# v5-Power-Section.net
KiCad netlist of a schematic drawn in EAGLE
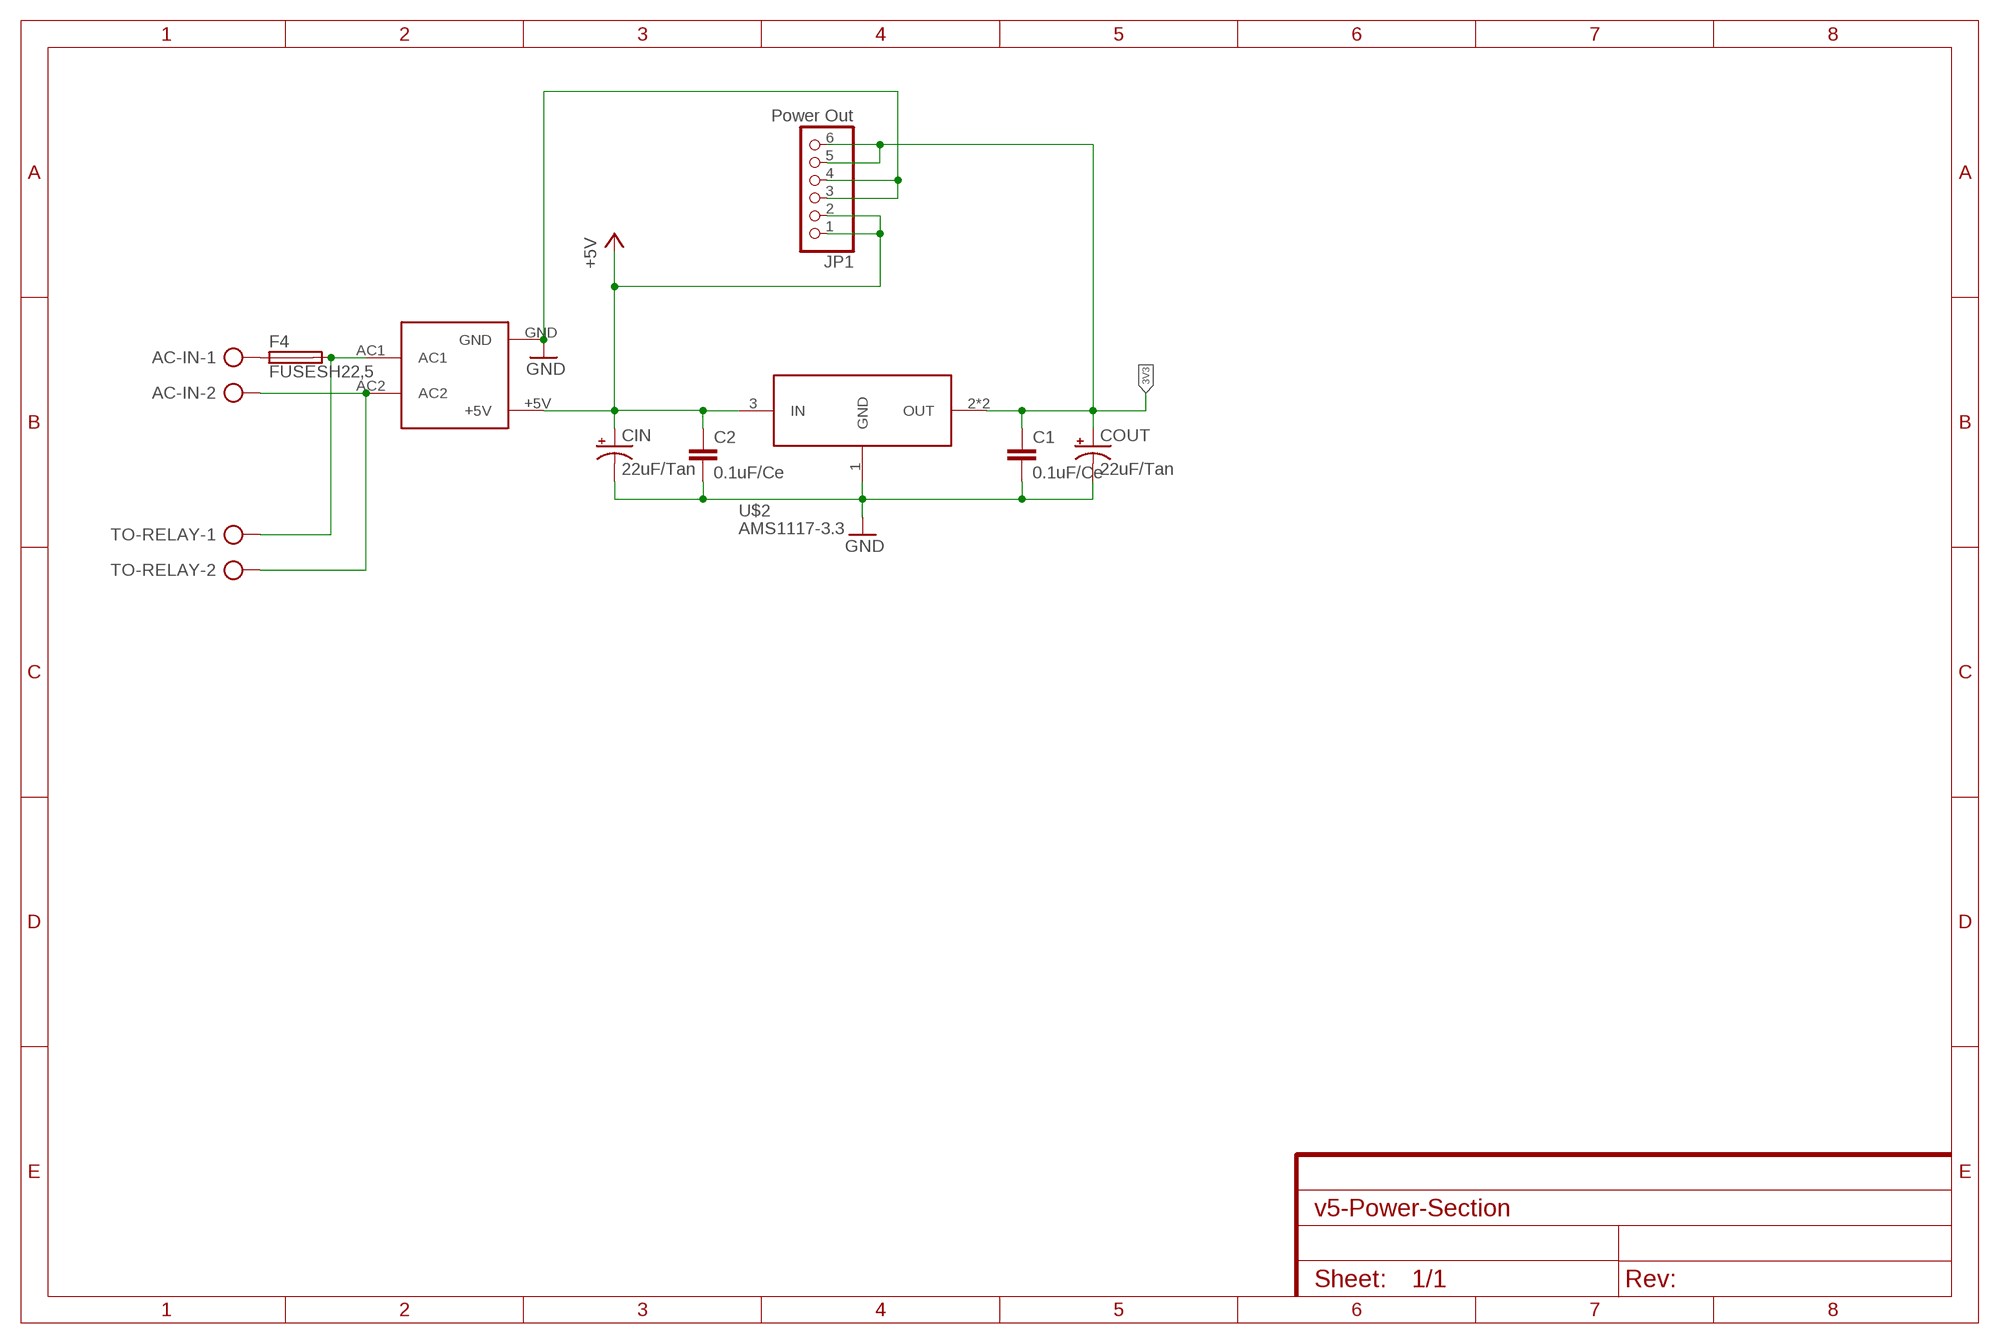
[diagram p0: schematic, sheet 1]

(export (version "E")
  (design (tool "Eeschema 10.0.6"))
  (components
    (comp (ref "AC-IN")
      (value "AK300/2")
      (footprint "eagle-import:AK300_2")
      (libsource (lib "eagle-import") (part "AK300/2"))
    )
    (comp (ref "C1")
      (value "0.1uF/Ce")
      (footprint "eagle-import:C025-024X044")
      (libsource (lib "eagle-import") (part "C-EU025-024X044"))
    )
    (comp (ref "C2")
      (value "0.1uF/Ce")
      (footprint "eagle-import:C025-024X044")
      (libsource (lib "eagle-import") (part "C-EU025-024X044"))
    )
    (comp (ref "CIN")
      (value "22uF/Tan")
      (footprint "eagle-import:E2,5-5")
      (libsource (lib "eagle-import") (part "CPOL-USE2.5-5"))
    )
    (comp (ref "COUT")
      (value "22uF/Tan")
      (footprint "eagle-import:E2,5-5")
      (libsource (lib "eagle-import") (part "CPOL-USE2.5-5"))
    )
    (comp (ref "F4")
      (value "FUSESH22,5")
      (footprint "eagle-import:SH22,5")
      (libsource (lib "eagle-import") (part "FUSESH22,5"))
    )
    (comp (ref "JP1")
      (value "Power Out")
      (footprint "eagle-import:1X06")
      (libsource (lib "eagle-import") (part "PINHD-1X6"))
    )
    (comp (ref "TO-RELAY")
      (value "AK300/2")
      (footprint "eagle-import:AK300_2")
      (libsource (lib "eagle-import") (part "AK300/2"))
    )
    (comp (ref "U$1")
      (value "HLK-PM01")
      (footprint "eagle-import:HLK-PM01")
      (libsource (lib "eagle-import") (part "HLK-PM01"))
    )
    (comp (ref "U$2")
      (value "AMS1117-3.3")
      (footprint "eagle-import:SOT-223")
      (libsource (lib "eagle-import") (part "AMS1117-3.3"))
    )
  )
  (nets
    (net (code "1") (name "+5V") (class "Default")
      (node (ref "C2") (pin "1") (pinfunction "1_1") (pintype "passive"))
      (node (ref "CIN") (pin "+") (pinfunction "+_+") (pintype "passive"))
      (node (ref "JP1") (pin "1") (pinfunction "1_1") (pintype "passive"))
      (node (ref "JP1") (pin "2") (pinfunction "2_2") (pintype "passive"))
      (node (ref "U$1") (pin "+5V") (pinfunction "+5V_+5V") (pintype "bidirectional"))
      (node (ref "U$2") (pin "3") (pinfunction "IN_3") (pintype "input"))
    )
    (net (code "2") (name "3V3") (class "Default")
      (node (ref "C1") (pin "1") (pinfunction "1_1") (pintype "passive"))
      (node (ref "COUT") (pin "+") (pinfunction "+_+") (pintype "passive"))
      (node (ref "JP1") (pin "5") (pinfunction "5_5") (pintype "passive"))
      (node (ref "JP1") (pin "6") (pinfunction "6_6") (pintype "passive"))
      (node (ref "U$2") (pin "2") (pinfunction "OUT_2") (pintype "output"))
      (node (ref "U$2") (pin "4") (pinfunction "OUT_4") (pintype "output"))
    )
    (net (code "3") (name "GND") (class "Default")
      (node (ref "C1") (pin "2") (pinfunction "2_2") (pintype "passive"))
      (node (ref "C2") (pin "2") (pinfunction "2_2") (pintype "passive"))
      (node (ref "CIN") (pin "-") (pinfunction "-_-") (pintype "passive"))
      (node (ref "COUT") (pin "-") (pinfunction "-_-") (pintype "passive"))
      (node (ref "JP1") (pin "3") (pinfunction "3_3") (pintype "passive"))
      (node (ref "JP1") (pin "4") (pinfunction "4_4") (pintype "passive"))
      (node (ref "U$1") (pin "GND") (pinfunction "GND_GND") (pintype "bidirectional"))
      (node (ref "U$2") (pin "1") (pinfunction "GND_1") (pintype "passive"))
    )
    (net (code "4") (name "Net-(AC-INA-KL)") (class "Default")
      (node (ref "AC-IN") (pin "1") (pinfunction "KL_1") (pintype "passive"))
      (node (ref "F4") (pin "1") (pinfunction "1_1") (pintype "passive"))
    )
    (net (code "5") (name "Net-(AC-INB-KL)") (class "Default")
      (node (ref "AC-IN") (pin "2") (pinfunction "KL_2") (pintype "passive"))
      (node (ref "TO-RELAY") (pin "2") (pinfunction "KL_2") (pintype "passive"))
      (node (ref "U$1") (pin "AC2") (pinfunction "AC2_AC2") (pintype "bidirectional"))
    )
    (net (code "6") (name "Net-(TO-RELAYA-KL)") (class "Default")
      (node (ref "F4") (pin "2") (pinfunction "2_2") (pintype "passive"))
      (node (ref "TO-RELAY") (pin "1") (pinfunction "KL_1") (pintype "passive"))
      (node (ref "U$1") (pin "AC1") (pinfunction "AC1_AC1") (pintype "bidirectional"))
    )
  )
)
